# MAX4239basedV3.net
KiCad netlist of a schematic drawn in EAGLE
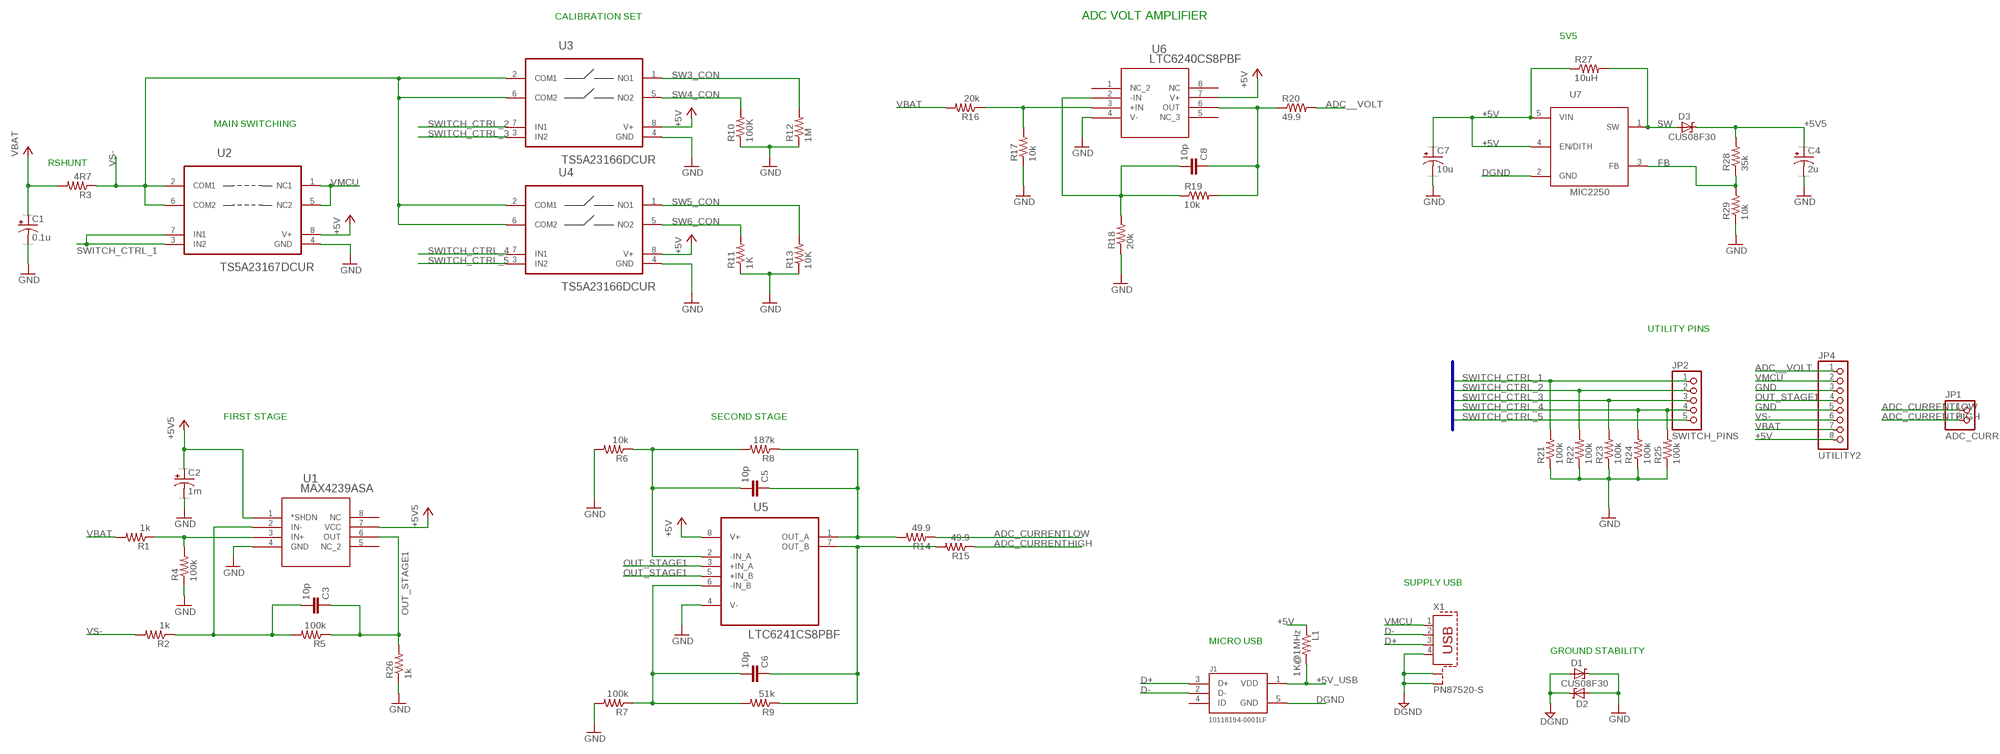
[diagram p0: schematic, sheet 1]

(export (version "E")
  (design (tool "Eeschema 10.0.6"))
  (components
    (comp (ref "C1")
      (value "0.1u")
      (footprint "eagle-import:PANASONIC_B")
      (libsource (lib "eagle-import") (part "CPOL-USB"))
    )
    (comp (ref "C2")
      (value "1m")
      (footprint "eagle-import:PANASONIC_B")
      (libsource (lib "eagle-import") (part "CPOL-USB"))
    )
    (comp (ref "C3")
      (value "10p")
      (footprint "eagle-import:C0805")
      (libsource (lib "eagle-import") (part "C-EUC0805"))
    )
    (comp (ref "C4")
      (value "2u")
      (footprint "eagle-import:PANASONIC_B")
      (libsource (lib "eagle-import") (part "CPOL-USB"))
    )
    (comp (ref "C5")
      (value "10p")
      (footprint "eagle-import:C0805")
      (libsource (lib "eagle-import") (part "C-EUC0805"))
    )
    (comp (ref "C6")
      (value "10p")
      (footprint "eagle-import:C0805")
      (libsource (lib "eagle-import") (part "C-EUC0805"))
    )
    (comp (ref "C7")
      (value "10u")
      (footprint "eagle-import:PANASONIC_B")
      (libsource (lib "eagle-import") (part "CPOL-USB"))
    )
    (comp (ref "C8")
      (value "10p")
      (footprint "eagle-import:C0805")
      (libsource (lib "eagle-import") (part "C-EUC0805"))
    )
    (comp (ref "D1")
      (value "CUS08F30")
      (footprint "eagle-import:SOD323")
      (fields (field (name "MF") "TOSHIBA"))
      (libsource (lib "eagle-import") (part "CUS08F30"))
    )
    (comp (ref "D2")
      (value "CUS08F30")
      (footprint "eagle-import:SOD323")
      (fields (field (name "MF") "TOSHIBA"))
      (libsource (lib "eagle-import") (part "CUS08F30"))
    )
    (comp (ref "D3")
      (value "CUS08F30")
      (footprint "eagle-import:SOD323")
      (fields (field (name "MF") "TOSHIBA"))
      (libsource (lib "eagle-import") (part "CUS08F30"))
    )
    (comp (ref "J1")
      (value "10118194-0001LF")
      (footprint "eagle-import:FRAMATOME_10118194-0001LF")
      (fields (field (name "MF") "Amphenol"))
      (libsource (lib "eagle-import") (part "10118194-0001LF"))
    )
    (comp (ref "JP1")
      (value "ADC_CURR")
      (footprint "eagle-import:1X02")
      (libsource (lib "eagle-import") (part "PINHD-1X2"))
    )
    (comp (ref "JP2")
      (value "SWITCH_PINS")
      (footprint "eagle-import:1X05")
      (libsource (lib "eagle-import") (part "PINHD-1X5"))
    )
    (comp (ref "JP4")
      (value "UTILITY2")
      (footprint "eagle-import:1X08")
      (libsource (lib "eagle-import") (part "PINHD-1X8"))
    )
    (comp (ref "L1")
      (value "1K@1MHz")
      (footprint "eagle-import:R0805")
      (libsource (lib "eagle-import") (part "R-US_R0805"))
    )
    (comp (ref "R1")
      (value "1k")
      (footprint "eagle-import:R0805")
      (libsource (lib "eagle-import") (part "R-US_R0805"))
    )
    (comp (ref "R2")
      (value "1k")
      (footprint "eagle-import:R0805")
      (libsource (lib "eagle-import") (part "R-US_R0805"))
    )
    (comp (ref "R3")
      (value "4R7")
      (footprint "eagle-import:R0805")
      (libsource (lib "eagle-import") (part "R-US_R0805"))
    )
    (comp (ref "R4")
      (value "100k")
      (footprint "eagle-import:R0805")
      (libsource (lib "eagle-import") (part "R-US_R0805"))
    )
    (comp (ref "R5")
      (value "100k")
      (footprint "eagle-import:R0805")
      (libsource (lib "eagle-import") (part "R-US_R0805"))
    )
    (comp (ref "R6")
      (value "10k")
      (footprint "eagle-import:R0805")
      (libsource (lib "eagle-import") (part "R-US_R0805"))
    )
    (comp (ref "R7")
      (value "100k")
      (footprint "eagle-import:R0805")
      (libsource (lib "eagle-import") (part "R-US_R0805"))
    )
    (comp (ref "R8")
      (value "187k")
      (footprint "eagle-import:R0805")
      (libsource (lib "eagle-import") (part "R-US_R0805"))
    )
    (comp (ref "R9")
      (value "51k")
      (footprint "eagle-import:R0805")
      (libsource (lib "eagle-import") (part "R-US_R0805"))
    )
    (comp (ref "R10")
      (value "100K")
      (footprint "eagle-import:R0805")
      (libsource (lib "eagle-import") (part "R-US_R0805"))
    )
    (comp (ref "R11")
      (value "1K")
      (footprint "eagle-import:R0805")
      (libsource (lib "eagle-import") (part "R-US_R0805"))
    )
    (comp (ref "R12")
      (value "1M")
      (footprint "eagle-import:R0805")
      (libsource (lib "eagle-import") (part "R-US_R0805"))
    )
    (comp (ref "R13")
      (value "10K")
      (footprint "eagle-import:R0805")
      (libsource (lib "eagle-import") (part "R-US_R0805"))
    )
    (comp (ref "R14")
      (value "49.9")
      (footprint "eagle-import:R0805")
      (libsource (lib "eagle-import") (part "R-US_R0805"))
    )
    (comp (ref "R15")
      (value "49.9")
      (footprint "eagle-import:R0805")
      (libsource (lib "eagle-import") (part "R-US_R0805"))
    )
    (comp (ref "R16")
      (value "20k")
      (footprint "eagle-import:R0805")
      (libsource (lib "eagle-import") (part "R-US_R0805"))
    )
    (comp (ref "R17")
      (value "10k")
      (footprint "eagle-import:R0805")
      (libsource (lib "eagle-import") (part "R-US_R0805"))
    )
    (comp (ref "R18")
      (value "20k")
      (footprint "eagle-import:R0805")
      (libsource (lib "eagle-import") (part "R-US_R0805"))
    )
    (comp (ref "R19")
      (value "10k")
      (footprint "eagle-import:R0805")
      (libsource (lib "eagle-import") (part "R-US_R0805"))
    )
    (comp (ref "R20")
      (value "49.9")
      (footprint "eagle-import:R0805")
      (libsource (lib "eagle-import") (part "R-US_R0805"))
    )
    (comp (ref "R21")
      (value "100k")
      (footprint "eagle-import:R0805")
      (libsource (lib "eagle-import") (part "R-US_R0805"))
    )
    (comp (ref "R22")
      (value "100k")
      (footprint "eagle-import:R0805")
      (libsource (lib "eagle-import") (part "R-US_R0805"))
    )
    (comp (ref "R23")
      (value "100k")
      (footprint "eagle-import:R0805")
      (libsource (lib "eagle-import") (part "R-US_R0805"))
    )
    (comp (ref "R24")
      (value "100k")
      (footprint "eagle-import:R0805")
      (libsource (lib "eagle-import") (part "R-US_R0805"))
    )
    (comp (ref "R25")
      (value "100k")
      (footprint "eagle-import:R0805")
      (libsource (lib "eagle-import") (part "R-US_R0805"))
    )
    (comp (ref "R26")
      (value "1k")
      (footprint "eagle-import:R0805")
      (libsource (lib "eagle-import") (part "R-US_R0805"))
    )
    (comp (ref "R27")
      (value "10uH")
      (footprint "eagle-import:R1210")
      (libsource (lib "eagle-import") (part "R-US_R1210"))
    )
    (comp (ref "R28")
      (value "35k")
      (footprint "eagle-import:R0805")
      (libsource (lib "eagle-import") (part "R-US_R0805"))
    )
    (comp (ref "R29")
      (value "10k")
      (footprint "eagle-import:R0805")
      (libsource (lib "eagle-import") (part "R-US_R0805"))
    )
    (comp (ref "U1")
      (value "MAX4239ASA")
      (footprint "eagle-import:21-0041B_8")
      (fields (field (name "MF") "Maxim Integrated") (field (name "MP") "MAX4239ASA+"))
      (libsource (lib "eagle-import") (part "MAX4239ASA"))
    )
    (comp (ref "U2")
      (value "TS5A23167DCUR")
      (footprint "eagle-import:SOP50P310X90-8N")
      (fields (field (name "MF") "Texas Instruments"))
      (libsource (lib "eagle-import") (part "TS5A23167DCUR"))
    )
    (comp (ref "U3")
      (value "TS5A23166DCUR")
      (footprint "eagle-import:SOP50P310X90-8N")
      (fields (field (name "MF") "Texas Instruments"))
      (libsource (lib "eagle-import") (part "TS5A23166DCUR"))
    )
    (comp (ref "U4")
      (value "TS5A23166DCUR")
      (footprint "eagle-import:SOP50P310X90-8N")
      (fields (field (name "MF") "Texas Instruments"))
      (libsource (lib "eagle-import") (part "TS5A23166DCUR"))
    )
    (comp (ref "U5")
      (value "LTC6241CS8PBF")
      (footprint "eagle-import:SOIC127P600X175-8N")
      (fields (field (name "MF") "Linear Technology") (field (name "MP") "LTC6241CS8#PBF"))
      (libsource (lib "eagle-import") (part "LTC6241CS8PBF"))
    )
    (comp (ref "U6")
      (value "LTC6240CS8PBF")
      (footprint "eagle-import:SO-8_S")
      (fields (field (name "MF") "Linear Technology") (field (name "MP") "LTC6240CS8#PBF"))
      (libsource (lib "eagle-import") (part "LTC6240CS8PBF"))
    )
    (comp (ref "U7")
      (value "MIC2250")
      (footprint "eagle-import:SOT95P270X145-5N")
      (fields (field (name "MF") "MICROCHIP"))
      (libsource (lib "eagle-import") (part "MIC2250"))
    )
    (comp (ref "X1")
      (value "PN87520-S")
      (footprint "eagle-import:PN87520-S")
      (libsource (lib "eagle-import") (part "PN87520-S"))
    )
  )
  (nets
    (net (code "1") (name "+5V") (class "Default")
      (node (ref "C7") (pin "+") (pinfunction "+_+") (pintype "passive"))
      (node (ref "JP4") (pin "8") (pinfunction "8_8") (pintype "passive"))
      (node (ref "L1") (pin "1") (pinfunction "1_1") (pintype "passive"))
      (node (ref "R27") (pin "1") (pinfunction "1_1") (pintype "passive"))
      (node (ref "U2") (pin "8") (pinfunction "V+_8") (pintype "power_in"))
      (node (ref "U3") (pin "8") (pinfunction "V+_8") (pintype "power_in"))
      (node (ref "U4") (pin "8") (pinfunction "V+_8") (pintype "power_in"))
      (node (ref "U5") (pin "8") (pinfunction "V+_8") (pintype "power_in"))
      (node (ref "U6") (pin "7") (pinfunction "V+_7") (pintype "power_in"))
      (node (ref "U7") (pin "4") (pinfunction "EN/DITH_4") (pintype "bidirectional"))
      (node (ref "U7") (pin "5") (pinfunction "VIN_5") (pintype "bidirectional"))
    )
    (net (code "2") (name "+5V5") (class "Default")
      (node (ref "C2") (pin "+") (pinfunction "+_+") (pintype "passive"))
      (node (ref "C4") (pin "+") (pinfunction "+_+") (pintype "passive"))
      (node (ref "D3") (pin "C") (pinfunction "C_C") (pintype "passive"))
      (node (ref "R28") (pin "2") (pinfunction "2_2") (pintype "passive"))
      (node (ref "U1") (pin "1") (pinfunction "*SHDN_1") (pintype "passive"))
      (node (ref "U1") (pin "7") (pinfunction "VCC_7") (pintype "power_in"))
    )
    (net (code "3") (name "/+5V_USB") (class "Default")
      (node (ref "J1") (pin "1") (pinfunction "VDD_1") (pintype "power_in"))
      (node (ref "L1") (pin "2") (pinfunction "2_2") (pintype "passive"))
    )
    (net (code "4") (name "/ADC_CURRENTHIGH") (class "Default")
      (node (ref "JP1") (pin "2") (pinfunction "2_2") (pintype "passive"))
      (node (ref "R15") (pin "1") (pinfunction "1_1") (pintype "passive"))
    )
    (net (code "5") (name "/ADC_CURRENTLOW") (class "Default")
      (node (ref "JP1") (pin "1") (pinfunction "1_1") (pintype "passive"))
      (node (ref "R14") (pin "1") (pinfunction "1_1") (pintype "passive"))
    )
    (net (code "6") (name "/ADC__VOLT") (class "Default")
      (node (ref "JP4") (pin "1") (pinfunction "1_1") (pintype "passive"))
      (node (ref "R20") (pin "2") (pinfunction "2_2") (pintype "passive"))
    )
    (net (code "7") (name "/D+") (class "Default")
      (node (ref "J1") (pin "3") (pinfunction "D+_3") (pintype "bidirectional"))
      (node (ref "X1") (pin "3") (pinfunction "3_3") (pintype "passive"))
    )
    (net (code "8") (name "/D-") (class "Default")
      (node (ref "J1") (pin "2") (pinfunction "D-_2") (pintype "bidirectional"))
      (node (ref "X1") (pin "2") (pinfunction "2_2") (pintype "passive"))
    )
    (net (code "9") (name "/FB") (class "Default")
      (node (ref "R28") (pin "1") (pinfunction "1_1") (pintype "passive"))
      (node (ref "R29") (pin "2") (pinfunction "2_2") (pintype "passive"))
      (node (ref "U7") (pin "3") (pinfunction "FB_3") (pintype "bidirectional"))
    )
    (net (code "10") (name "/OUT_STAGE1") (class "Default")
      (node (ref "C3") (pin "1") (pinfunction "1_1") (pintype "passive"))
      (node (ref "JP4") (pin "4") (pinfunction "4_4") (pintype "passive"))
      (node (ref "R26") (pin "2") (pinfunction "2_2") (pintype "passive"))
      (node (ref "R5") (pin "1") (pinfunction "1_1") (pintype "passive"))
      (node (ref "U1") (pin "6") (pinfunction "OUT_6") (pintype "output"))
      (node (ref "U5") (pin "3") (pinfunction "+IN_A_3") (pintype "input"))
      (node (ref "U5") (pin "5") (pinfunction "+IN_B_5") (pintype "input"))
    )
    (net (code "11") (name "/SW") (class "Default")
      (node (ref "D3") (pin "A") (pinfunction "A_A") (pintype "passive"))
      (node (ref "R27") (pin "2") (pinfunction "2_2") (pintype "passive"))
      (node (ref "U7") (pin "1") (pinfunction "SW_1") (pintype "bidirectional"))
    )
    (net (code "12") (name "/SW3_CON") (class "Default")
      (node (ref "R12") (pin "2") (pinfunction "2_2") (pintype "passive"))
      (node (ref "U3") (pin "1") (pinfunction "NO1_1") (pintype "bidirectional"))
    )
    (net (code "13") (name "/SW4_CON") (class "Default")
      (node (ref "R10") (pin "2") (pinfunction "2_2") (pintype "passive"))
      (node (ref "U3") (pin "5") (pinfunction "NO2_5") (pintype "bidirectional"))
    )
    (net (code "14") (name "/SW5_CON") (class "Default")
      (node (ref "R13") (pin "2") (pinfunction "2_2") (pintype "passive"))
      (node (ref "U4") (pin "1") (pinfunction "NO1_1") (pintype "bidirectional"))
    )
    (net (code "15") (name "/SW6_CON") (class "Default")
      (node (ref "R11") (pin "2") (pinfunction "2_2") (pintype "passive"))
      (node (ref "U4") (pin "5") (pinfunction "NO2_5") (pintype "bidirectional"))
    )
    (net (code "16") (name "/SWITCH_CTRL_1") (class "Default")
      (node (ref "JP2") (pin "1") (pinfunction "1_1") (pintype "passive"))
      (node (ref "R21") (pin "2") (pinfunction "2_2") (pintype "passive"))
      (node (ref "U2") (pin "3") (pinfunction "IN2_3") (pintype "input"))
      (node (ref "U2") (pin "7") (pinfunction "IN1_7") (pintype "input"))
    )
    (net (code "17") (name "/SWITCH_CTRL_2") (class "Default")
      (node (ref "JP2") (pin "2") (pinfunction "2_2") (pintype "passive"))
      (node (ref "R22") (pin "2") (pinfunction "2_2") (pintype "passive"))
      (node (ref "U3") (pin "7") (pinfunction "IN1_7") (pintype "input"))
    )
    (net (code "18") (name "/SWITCH_CTRL_3") (class "Default")
      (node (ref "JP2") (pin "3") (pinfunction "3_3") (pintype "passive"))
      (node (ref "R23") (pin "2") (pinfunction "2_2") (pintype "passive"))
      (node (ref "U3") (pin "3") (pinfunction "IN2_3") (pintype "input"))
    )
    (net (code "19") (name "/SWITCH_CTRL_4") (class "Default")
      (node (ref "JP2") (pin "4") (pinfunction "4_4") (pintype "passive"))
      (node (ref "R24") (pin "2") (pinfunction "2_2") (pintype "passive"))
      (node (ref "R25") (pin "2") (pinfunction "2_2") (pintype "passive"))
      (node (ref "U4") (pin "7") (pinfunction "IN1_7") (pintype "input"))
    )
    (net (code "20") (name "/SWITCH_CTRL_5") (class "Default")
      (node (ref "JP2") (pin "5") (pinfunction "5_5") (pintype "passive"))
      (node (ref "U4") (pin "3") (pinfunction "IN2_3") (pintype "input"))
    )
    (net (code "21") (name "/VMCU") (class "Default")
      (node (ref "JP4") (pin "2") (pinfunction "2_2") (pintype "passive"))
      (node (ref "U2") (pin "1") (pinfunction "NC1_1") (pintype "bidirectional"))
      (node (ref "U2") (pin "5") (pinfunction "NC2_5") (pintype "bidirectional"))
      (node (ref "X1") (pin "1") (pinfunction "1_1") (pintype "passive"))
    )
    (net (code "22") (name "/VS-") (class "Default")
      (node (ref "JP4") (pin "6") (pinfunction "6_6") (pintype "passive"))
      (node (ref "R2") (pin "2") (pinfunction "2_2") (pintype "passive"))
      (node (ref "R3") (pin "1") (pinfunction "1_1") (pintype "passive"))
      (node (ref "U2") (pin "2") (pinfunction "COM1_2") (pintype "bidirectional"))
      (node (ref "U2") (pin "6") (pinfunction "COM2_6") (pintype "bidirectional"))
      (node (ref "U3") (pin "2") (pinfunction "COM1_2") (pintype "bidirectional"))
      (node (ref "U3") (pin "6") (pinfunction "COM2_6") (pintype "bidirectional"))
      (node (ref "U4") (pin "2") (pinfunction "COM1_2") (pintype "bidirectional"))
      (node (ref "U4") (pin "6") (pinfunction "COM2_6") (pintype "bidirectional"))
    )
    (net (code "23") (name "DGND") (class "Default")
      (node (ref "D1") (pin "A") (pinfunction "A_A") (pintype "passive"))
      (node (ref "D2") (pin "C") (pinfunction "C_C") (pintype "passive"))
      (node (ref "J1") (pin "5") (pinfunction "GND_5") (pintype "power_in"))
      (node (ref "U7") (pin "2") (pinfunction "GND_2") (pintype "bidirectional"))
      (node (ref "X1") (pin "4") (pinfunction "4_4") (pintype "passive"))
      (node (ref "X1") (pin "S1") (pinfunction "S1_S1") (pintype "passive"))
      (node (ref "X1") (pin "S2") (pinfunction "S2_S2") (pintype "passive"))
    )
    (net (code "24") (name "GND") (class "Default")
      (node (ref "C1") (pin "-") (pinfunction "-_-") (pintype "passive"))
      (node (ref "C2") (pin "-") (pinfunction "-_-") (pintype "passive"))
      (node (ref "C4") (pin "-") (pinfunction "-_-") (pintype "passive"))
      (node (ref "C7") (pin "-") (pinfunction "-_-") (pintype "passive"))
      (node (ref "D1") (pin "C") (pinfunction "C_C") (pintype "passive"))
      (node (ref "D2") (pin "A") (pinfunction "A_A") (pintype "passive"))
      (node (ref "JP4") (pin "3") (pinfunction "3_3") (pintype "passive"))
      (node (ref "JP4") (pin "5") (pinfunction "5_5") (pintype "passive"))
      (node (ref "R10") (pin "1") (pinfunction "1_1") (pintype "passive"))
      (node (ref "R11") (pin "1") (pinfunction "1_1") (pintype "passive"))
      (node (ref "R12") (pin "1") (pinfunction "1_1") (pintype "passive"))
      (node (ref "R13") (pin "1") (pinfunction "1_1") (pintype "passive"))
      (node (ref "R17") (pin "1") (pinfunction "1_1") (pintype "passive"))
      (node (ref "R18") (pin "1") (pinfunction "1_1") (pintype "passive"))
      (node (ref "R21") (pin "1") (pinfunction "1_1") (pintype "passive"))
      (node (ref "R22") (pin "1") (pinfunction "1_1") (pintype "passive"))
      (node (ref "R23") (pin "1") (pinfunction "1_1") (pintype "passive"))
      (node (ref "R24") (pin "1") (pinfunction "1_1") (pintype "passive"))
      (node (ref "R25") (pin "1") (pinfunction "1_1") (pintype "passive"))
      (node (ref "R26") (pin "1") (pinfunction "1_1") (pintype "passive"))
      (node (ref "R29") (pin "1") (pinfunction "1_1") (pintype "passive"))
      (node (ref "R4") (pin "1") (pinfunction "1_1") (pintype "passive"))
      (node (ref "R6") (pin "2") (pinfunction "2_2") (pintype "passive"))
      (node (ref "R7") (pin "2") (pinfunction "2_2") (pintype "passive"))
      (node (ref "U1") (pin "4") (pinfunction "GND_4") (pintype "power_in"))
      (node (ref "U2") (pin "4") (pinfunction "GND_4") (pintype "passive"))
      (node (ref "U3") (pin "4") (pinfunction "GND_4") (pintype "passive"))
      (node (ref "U4") (pin "4") (pinfunction "GND_4") (pintype "passive"))
      (node (ref "U5") (pin "4") (pinfunction "V-_4") (pintype "power_in"))
      (node (ref "U6") (pin "4") (pinfunction "V-_4") (pintype "power_in"))
    )
    (net (code "25") (name "Net-(U1-IN+)") (class "Default")
      (node (ref "R1") (pin "1") (pinfunction "1_1") (pintype "passive"))
      (node (ref "R4") (pin "2") (pinfunction "2_2") (pintype "passive"))
      (node (ref "U1") (pin "3") (pinfunction "IN+_3") (pintype "input"))
    )
    (net (code "26") (name "Net-(U1-IN-)") (class "Default")
      (node (ref "C3") (pin "2") (pinfunction "2_2") (pintype "passive"))
      (node (ref "R2") (pin "1") (pinfunction "1_1") (pintype "passive"))
      (node (ref "R5") (pin "2") (pinfunction "2_2") (pintype "passive"))
      (node (ref "U1") (pin "2") (pinfunction "IN-_2") (pintype "input"))
    )
    (net (code "27") (name "Net-(U5--IN_A)") (class "Default")
      (node (ref "C5") (pin "2") (pinfunction "2_2") (pintype "passive"))
      (node (ref "R6") (pin "1") (pinfunction "1_1") (pintype "passive"))
      (node (ref "R8") (pin "2") (pinfunction "2_2") (pintype "passive"))
      (node (ref "U5") (pin "2") (pinfunction "-IN_A_2") (pintype "input"))
    )
    (net (code "28") (name "Net-(U5--IN_B)") (class "Default")
      (node (ref "C6") (pin "2") (pinfunction "2_2") (pintype "passive"))
      (node (ref "R7") (pin "1") (pinfunction "1_1") (pintype "passive"))
      (node (ref "R9") (pin "2") (pinfunction "2_2") (pintype "passive"))
      (node (ref "U5") (pin "6") (pinfunction "-IN_B_6") (pintype "input"))
    )
    (net (code "29") (name "Net-(U5-OUT_A)") (class "Default")
      (node (ref "C5") (pin "1") (pinfunction "1_1") (pintype "passive"))
      (node (ref "R14") (pin "2") (pinfunction "2_2") (pintype "passive"))
      (node (ref "R8") (pin "1") (pinfunction "1_1") (pintype "passive"))
      (node (ref "U5") (pin "1") (pinfunction "OUT_A_1") (pintype "output"))
    )
    (net (code "30") (name "Net-(U5-OUT_B)") (class "Default")
      (node (ref "C6") (pin "1") (pinfunction "1_1") (pintype "passive"))
      (node (ref "R15") (pin "2") (pinfunction "2_2") (pintype "passive"))
      (node (ref "R9") (pin "1") (pinfunction "1_1") (pintype "passive"))
      (node (ref "U5") (pin "7") (pinfunction "OUT_B_7") (pintype "output"))
    )
    (net (code "31") (name "Net-(U6-+IN)") (class "Default")
      (node (ref "R16") (pin "1") (pinfunction "1_1") (pintype "passive"))
      (node (ref "R17") (pin "2") (pinfunction "2_2") (pintype "passive"))
      (node (ref "U6") (pin "3") (pinfunction "+IN_3") (pintype "input"))
    )
    (net (code "32") (name "Net-(U6--IN)") (class "Default")
      (node (ref "C8") (pin "2") (pinfunction "2_2") (pintype "passive"))
      (node (ref "R18") (pin "2") (pinfunction "2_2") (pintype "passive"))
      (node (ref "R19") (pin "1") (pinfunction "1_1") (pintype "passive"))
      (node (ref "U6") (pin "2") (pinfunction "-IN_2") (pintype "input"))
    )
    (net (code "33") (name "Net-(U6-OUT)") (class "Default")
      (node (ref "C8") (pin "1") (pinfunction "1_1") (pintype "passive"))
      (node (ref "R19") (pin "2") (pinfunction "2_2") (pintype "passive"))
      (node (ref "R20") (pin "1") (pinfunction "1_1") (pintype "passive"))
      (node (ref "U6") (pin "6") (pinfunction "OUT_6") (pintype "output"))
    )
    (net (code "34") (name "VBAT") (class "Default")
      (node (ref "C1") (pin "+") (pinfunction "+_+") (pintype "passive"))
      (node (ref "JP4") (pin "7") (pinfunction "7_7") (pintype "passive"))
      (node (ref "R1") (pin "2") (pinfunction "2_2") (pintype "passive"))
      (node (ref "R16") (pin "2") (pinfunction "2_2") (pintype "passive"))
      (node (ref "R3") (pin "2") (pinfunction "2_2") (pintype "passive"))
    )
    (net (code "35") (name "unconnected-(J1-ID-Pad4)") (class "Default")
      (node (ref "J1") (pin "4") (pinfunction "ID_4") (pintype "passive"))
    )
    (net (code "36") (name "unconnected-(U1-NC-Pad8)") (class "Default")
      (node (ref "U1") (pin "8") (pinfunction "NC_8") (pintype "passive"))
    )
    (net (code "37") (name "unconnected-(U1-NC_2-Pad5)") (class "Default")
      (node (ref "U1") (pin "5") (pinfunction "NC_2_5") (pintype "passive"))
    )
    (net (code "38") (name "unconnected-(U6-NC-Pad8)") (class "Default")
      (node (ref "U6") (pin "8") (pinfunction "NC_8") (pintype "no_connect"))
    )
    (net (code "39") (name "unconnected-(U6-NC_2-Pad1)") (class "Default")
      (node (ref "U6") (pin "1") (pinfunction "NC_2_1") (pintype "no_connect"))
    )
    (net (code "40") (name "unconnected-(U6-NC_3-Pad5)") (class "Default")
      (node (ref "U6") (pin "5") (pinfunction "NC_3_5") (pintype "no_connect"))
    )
  )
)
